# QFN-20_5x5mm_Breakout.net
KiCad netlist of a schematic drawn in EAGLE
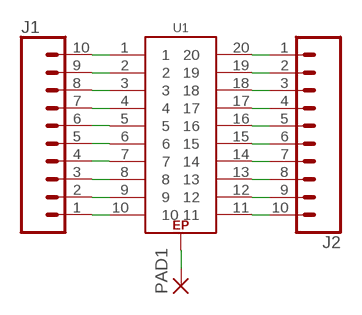
[diagram p0: schematic, sheet 1]

(export (version "E")
  (design (tool "Eeschema 10.0.6"))
  (components
    (comp (ref "J1")
      (value "CONN_10\"")
      (footprint "eagle-import:1X10")
      (libsource (lib "eagle-import") (part "CONN_10{dblquote}"))
    )
    (comp (ref "J2")
      (value "CONN_10\"")
      (footprint "eagle-import:1X10")
      (libsource (lib "eagle-import") (part "CONN_10{dblquote}"))
    )
    (comp (ref "PAD1")
      (value "SMD2")
      (footprint "eagle-import:SMD1,27-2,54")
      (fields (field (name "MPN") "DNP"))
      (libsource (lib "eagle-import") (part "SMD2"))
    )
    (comp (ref "U1")
      (value "GEN_20_EPQFN-20_5X5")
      (footprint "eagle-import:QFN20_5X5")
      (libsource (lib "eagle-import") (part "GEN_20_EPQFN-20_5X5"))
    )
  )
  (nets
    (net (code "1") (name "Net-(J1-Pad1)") (class "Default")
      (node (ref "J1") (pin "1") (pinfunction "1_1") (pintype "passive"))
      (node (ref "U1") (pin "10") (pinfunction "10_10") (pintype "bidirectional"))
    )
    (net (code "2") (name "Net-(J1-Pad2)") (class "Default")
      (node (ref "J1") (pin "2") (pinfunction "2_2") (pintype "passive"))
      (node (ref "U1") (pin "9") (pinfunction "9_9") (pintype "bidirectional"))
    )
    (net (code "3") (name "Net-(J1-Pad3)") (class "Default")
      (node (ref "J1") (pin "3") (pinfunction "3_3") (pintype "passive"))
      (node (ref "U1") (pin "8") (pinfunction "8_8") (pintype "bidirectional"))
    )
    (net (code "4") (name "Net-(J1-Pad4)") (class "Default")
      (node (ref "J1") (pin "4") (pinfunction "4_4") (pintype "passive"))
      (node (ref "U1") (pin "7") (pinfunction "7_7") (pintype "bidirectional"))
    )
    (net (code "5") (name "Net-(J1-Pad5)") (class "Default")
      (node (ref "J1") (pin "5") (pinfunction "5_5") (pintype "passive"))
      (node (ref "U1") (pin "6") (pinfunction "6_6") (pintype "bidirectional"))
    )
    (net (code "6") (name "Net-(J1-Pad6)") (class "Default")
      (node (ref "J1") (pin "6") (pinfunction "6_6") (pintype "passive"))
      (node (ref "U1") (pin "5") (pinfunction "5_5") (pintype "bidirectional"))
    )
    (net (code "7") (name "Net-(J1-Pad7)") (class "Default")
      (node (ref "J1") (pin "7") (pinfunction "7_7") (pintype "passive"))
      (node (ref "U1") (pin "4") (pinfunction "4_4") (pintype "bidirectional"))
    )
    (net (code "8") (name "Net-(J1-Pad8)") (class "Default")
      (node (ref "J1") (pin "8") (pinfunction "8_8") (pintype "passive"))
      (node (ref "U1") (pin "3") (pinfunction "3_3") (pintype "bidirectional"))
    )
    (net (code "9") (name "Net-(J1-Pad9)") (class "Default")
      (node (ref "J1") (pin "9") (pinfunction "9_9") (pintype "passive"))
      (node (ref "U1") (pin "2") (pinfunction "2_2") (pintype "bidirectional"))
    )
    (net (code "10") (name "Net-(J1-Pad10)") (class "Default")
      (node (ref "J1") (pin "10") (pinfunction "10_10") (pintype "passive"))
      (node (ref "U1") (pin "1") (pinfunction "1_1") (pintype "bidirectional"))
    )
    (net (code "11") (name "Net-(J2-Pad1)") (class "Default")
      (node (ref "J2") (pin "1") (pinfunction "1_1") (pintype "passive"))
      (node (ref "U1") (pin "20") (pinfunction "20_20") (pintype "bidirectional"))
    )
    (net (code "12") (name "Net-(J2-Pad2)") (class "Default")
      (node (ref "J2") (pin "2") (pinfunction "2_2") (pintype "passive"))
      (node (ref "U1") (pin "19") (pinfunction "19_19") (pintype "bidirectional"))
    )
    (net (code "13") (name "Net-(J2-Pad3)") (class "Default")
      (node (ref "J2") (pin "3") (pinfunction "3_3") (pintype "passive"))
      (node (ref "U1") (pin "18") (pinfunction "18_18") (pintype "bidirectional"))
    )
    (net (code "14") (name "Net-(J2-Pad4)") (class "Default")
      (node (ref "J2") (pin "4") (pinfunction "4_4") (pintype "passive"))
      (node (ref "U1") (pin "17") (pinfunction "17_17") (pintype "bidirectional"))
    )
    (net (code "15") (name "Net-(J2-Pad5)") (class "Default")
      (node (ref "J2") (pin "5") (pinfunction "5_5") (pintype "passive"))
      (node (ref "U1") (pin "16") (pinfunction "16_16") (pintype "bidirectional"))
    )
    (net (code "16") (name "Net-(J2-Pad6)") (class "Default")
      (node (ref "J2") (pin "6") (pinfunction "6_6") (pintype "passive"))
      (node (ref "U1") (pin "15") (pinfunction "15_15") (pintype "bidirectional"))
    )
    (net (code "17") (name "Net-(J2-Pad7)") (class "Default")
      (node (ref "J2") (pin "7") (pinfunction "7_7") (pintype "passive"))
      (node (ref "U1") (pin "14") (pinfunction "14_14") (pintype "bidirectional"))
    )
    (net (code "18") (name "Net-(J2-Pad8)") (class "Default")
      (node (ref "J2") (pin "8") (pinfunction "8_8") (pintype "passive"))
      (node (ref "U1") (pin "13") (pinfunction "13_13") (pintype "bidirectional"))
    )
    (net (code "19") (name "Net-(J2-Pad9)") (class "Default")
      (node (ref "J2") (pin "9") (pinfunction "9_9") (pintype "passive"))
      (node (ref "U1") (pin "12") (pinfunction "12_12") (pintype "bidirectional"))
    )
    (net (code "20") (name "Net-(J2-Pad10)") (class "Default")
      (node (ref "J2") (pin "10") (pinfunction "10_10") (pintype "passive"))
      (node (ref "U1") (pin "11") (pinfunction "11_11") (pintype "bidirectional"))
    )
    (net (code "21") (name "Net-(PAD1-P)") (class "Default")
      (node (ref "PAD1") (pin "1") (pinfunction "P_1") (pintype "passive"))
      (node (ref "U1") (pin "EP") (pinfunction "EP_EP") (pintype "passive"))
    )
  )
)
